# BrushlessLamp.net
KiCad netlist of a schematic drawn in EAGLE
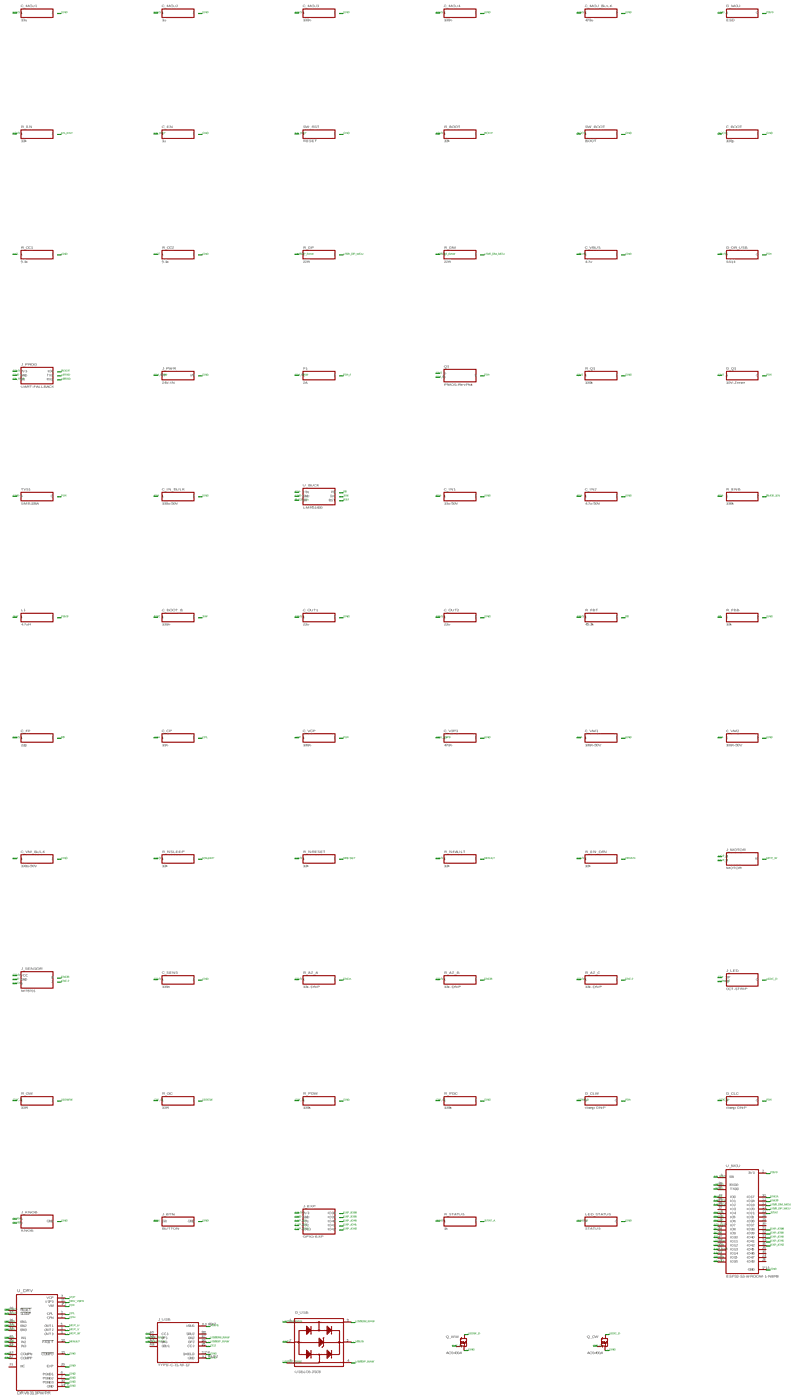
[diagram p0: schematic, sheet 1, overview]
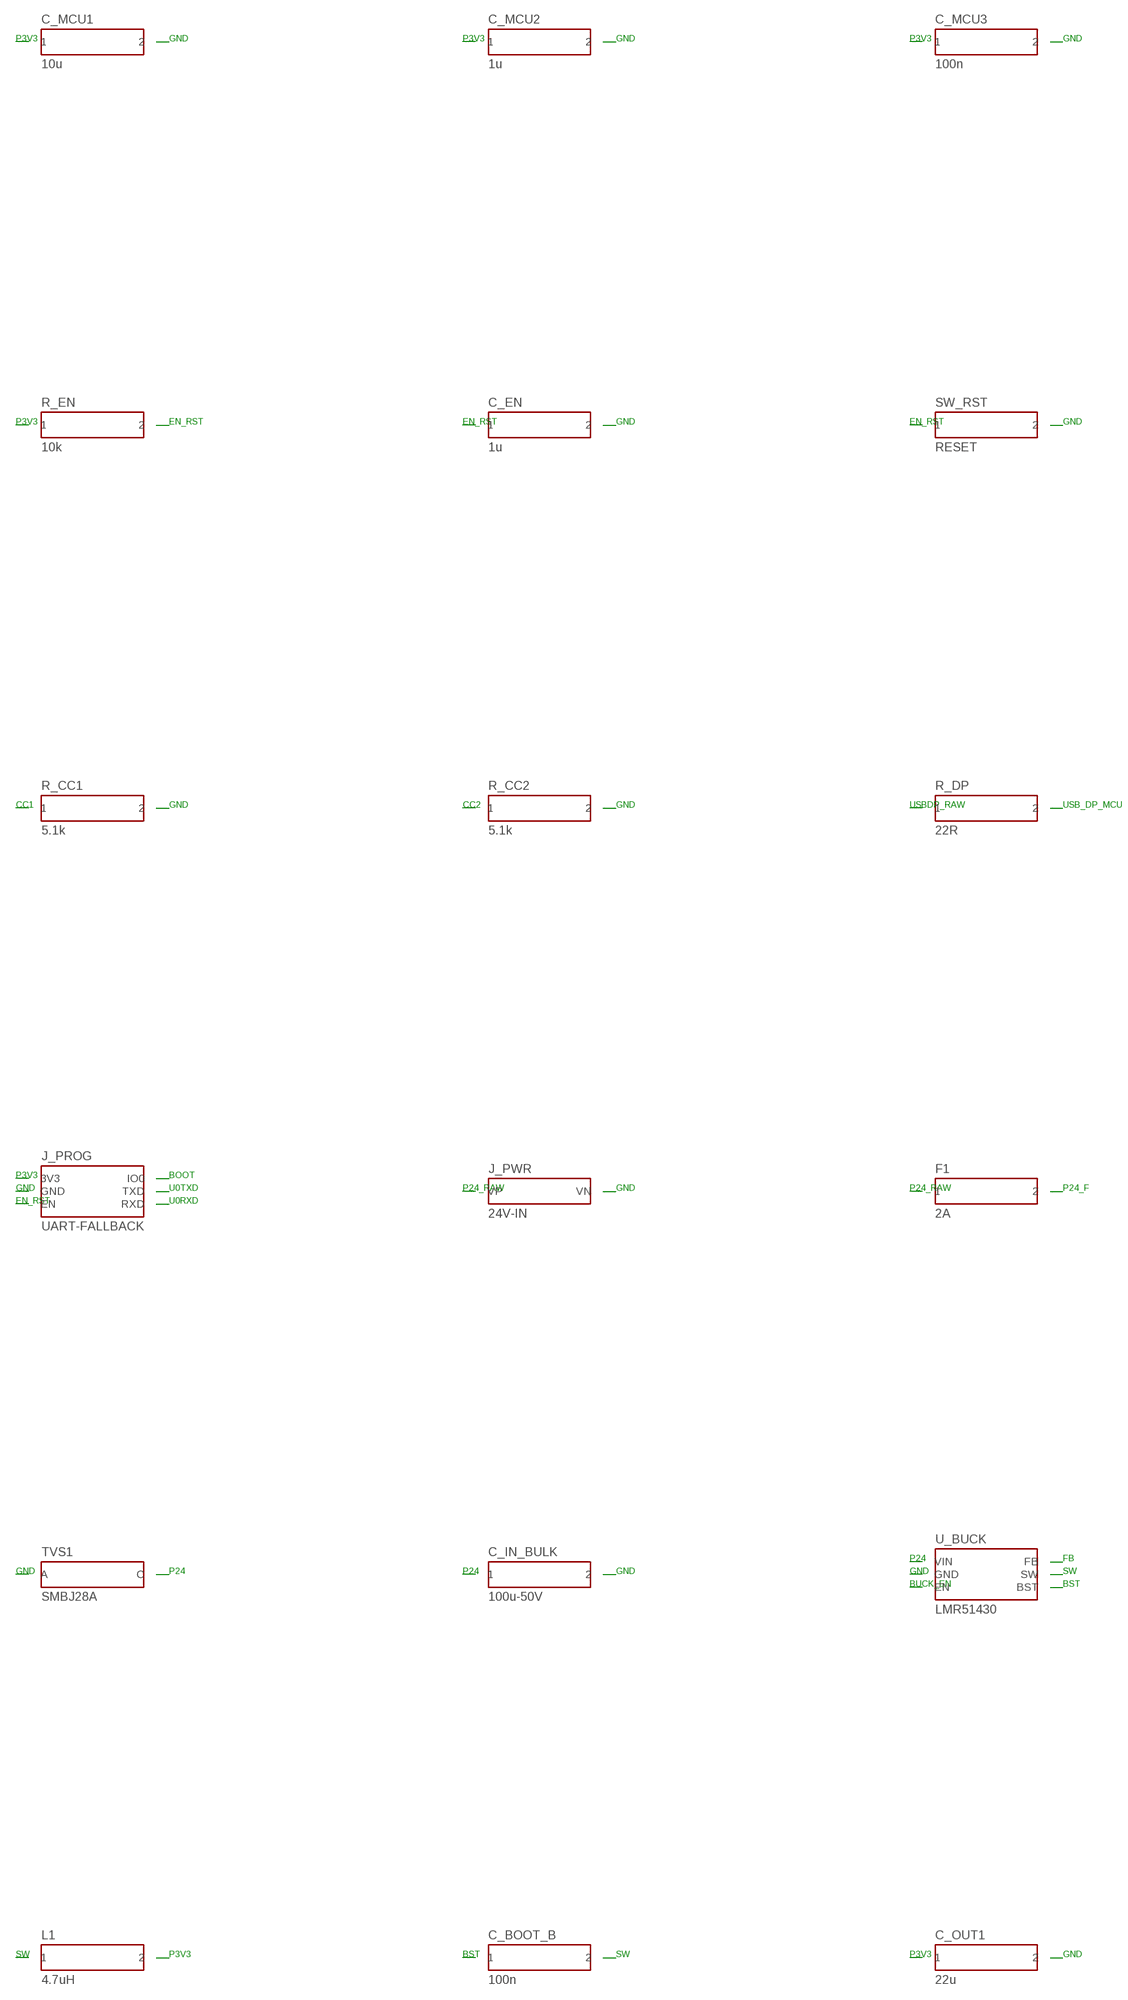
[diagram p1: schematic, sheet 1, part 1 of 4]
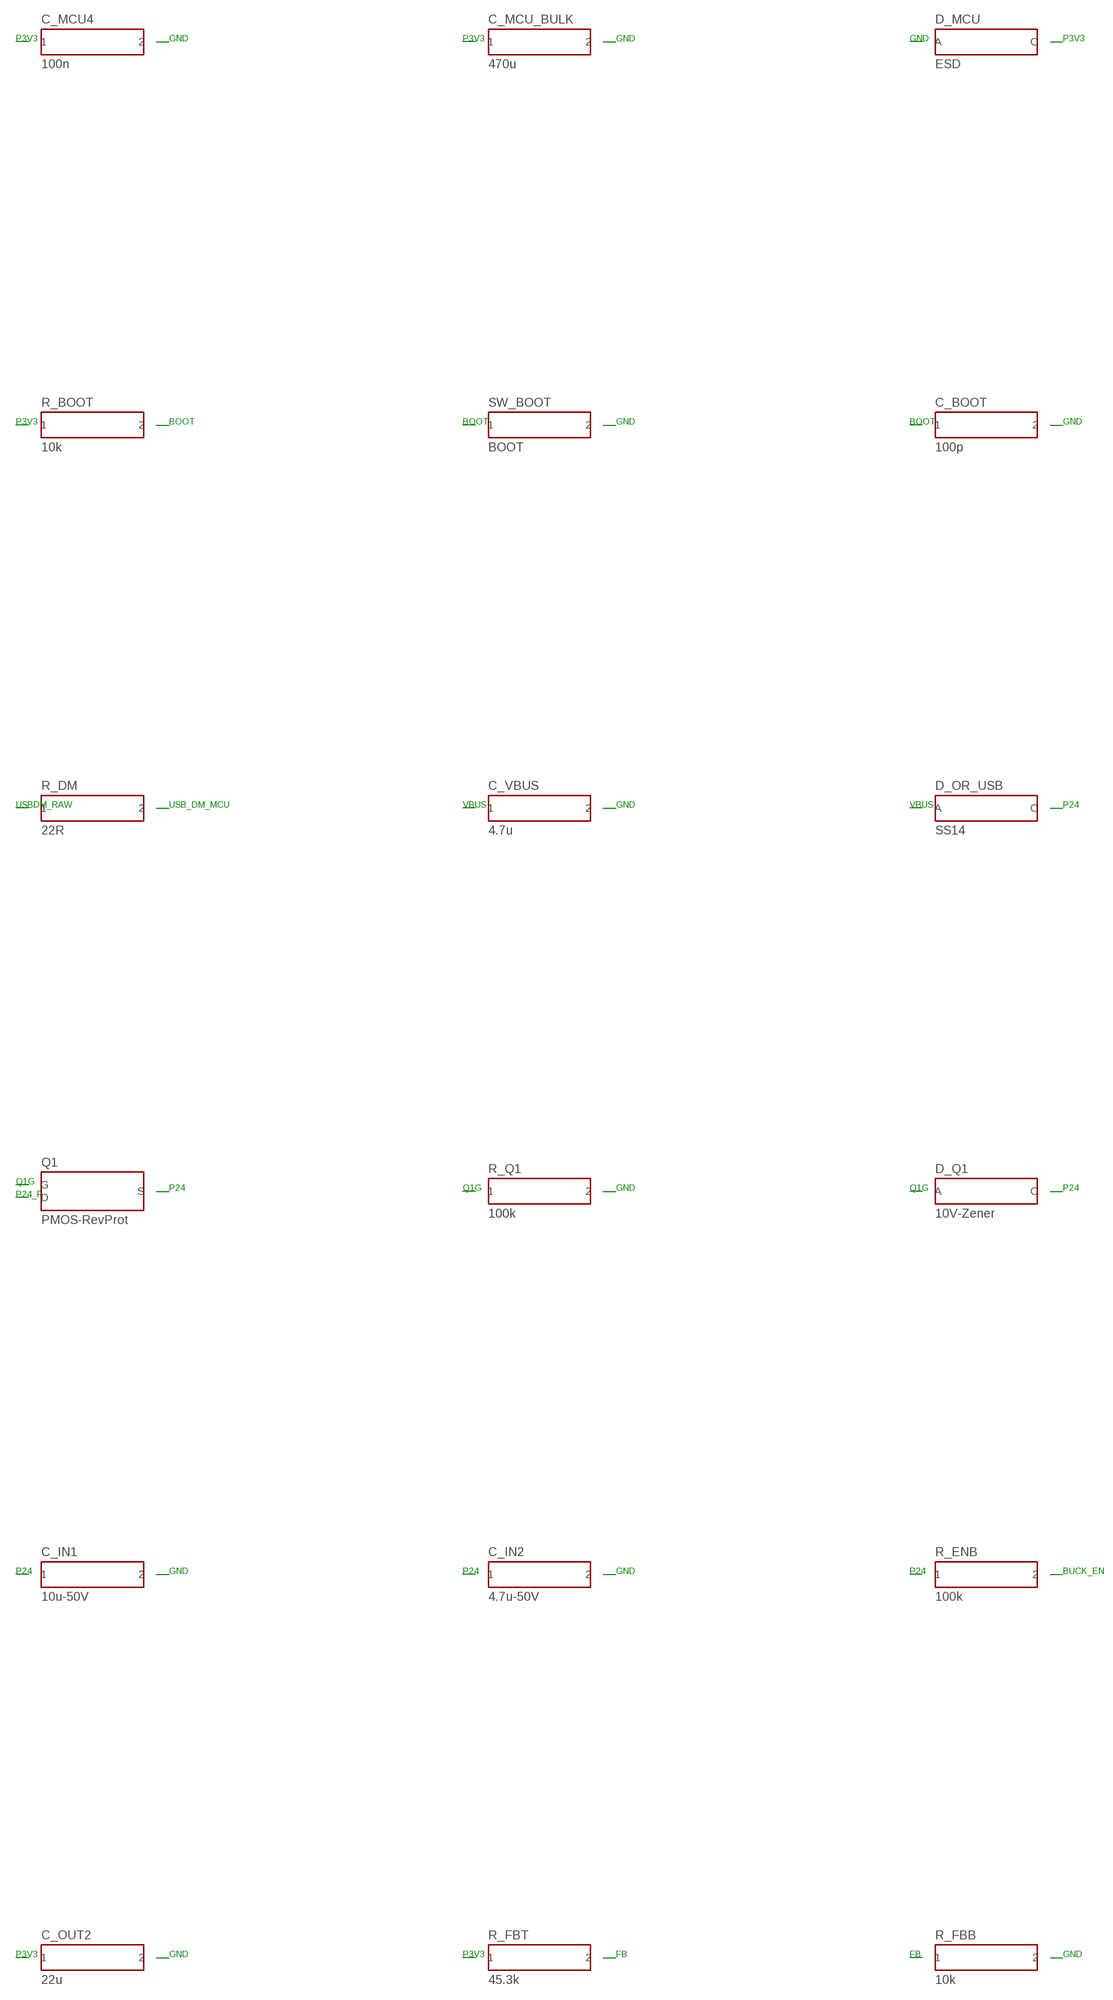
[diagram p2: schematic, sheet 1, part 2 of 4]
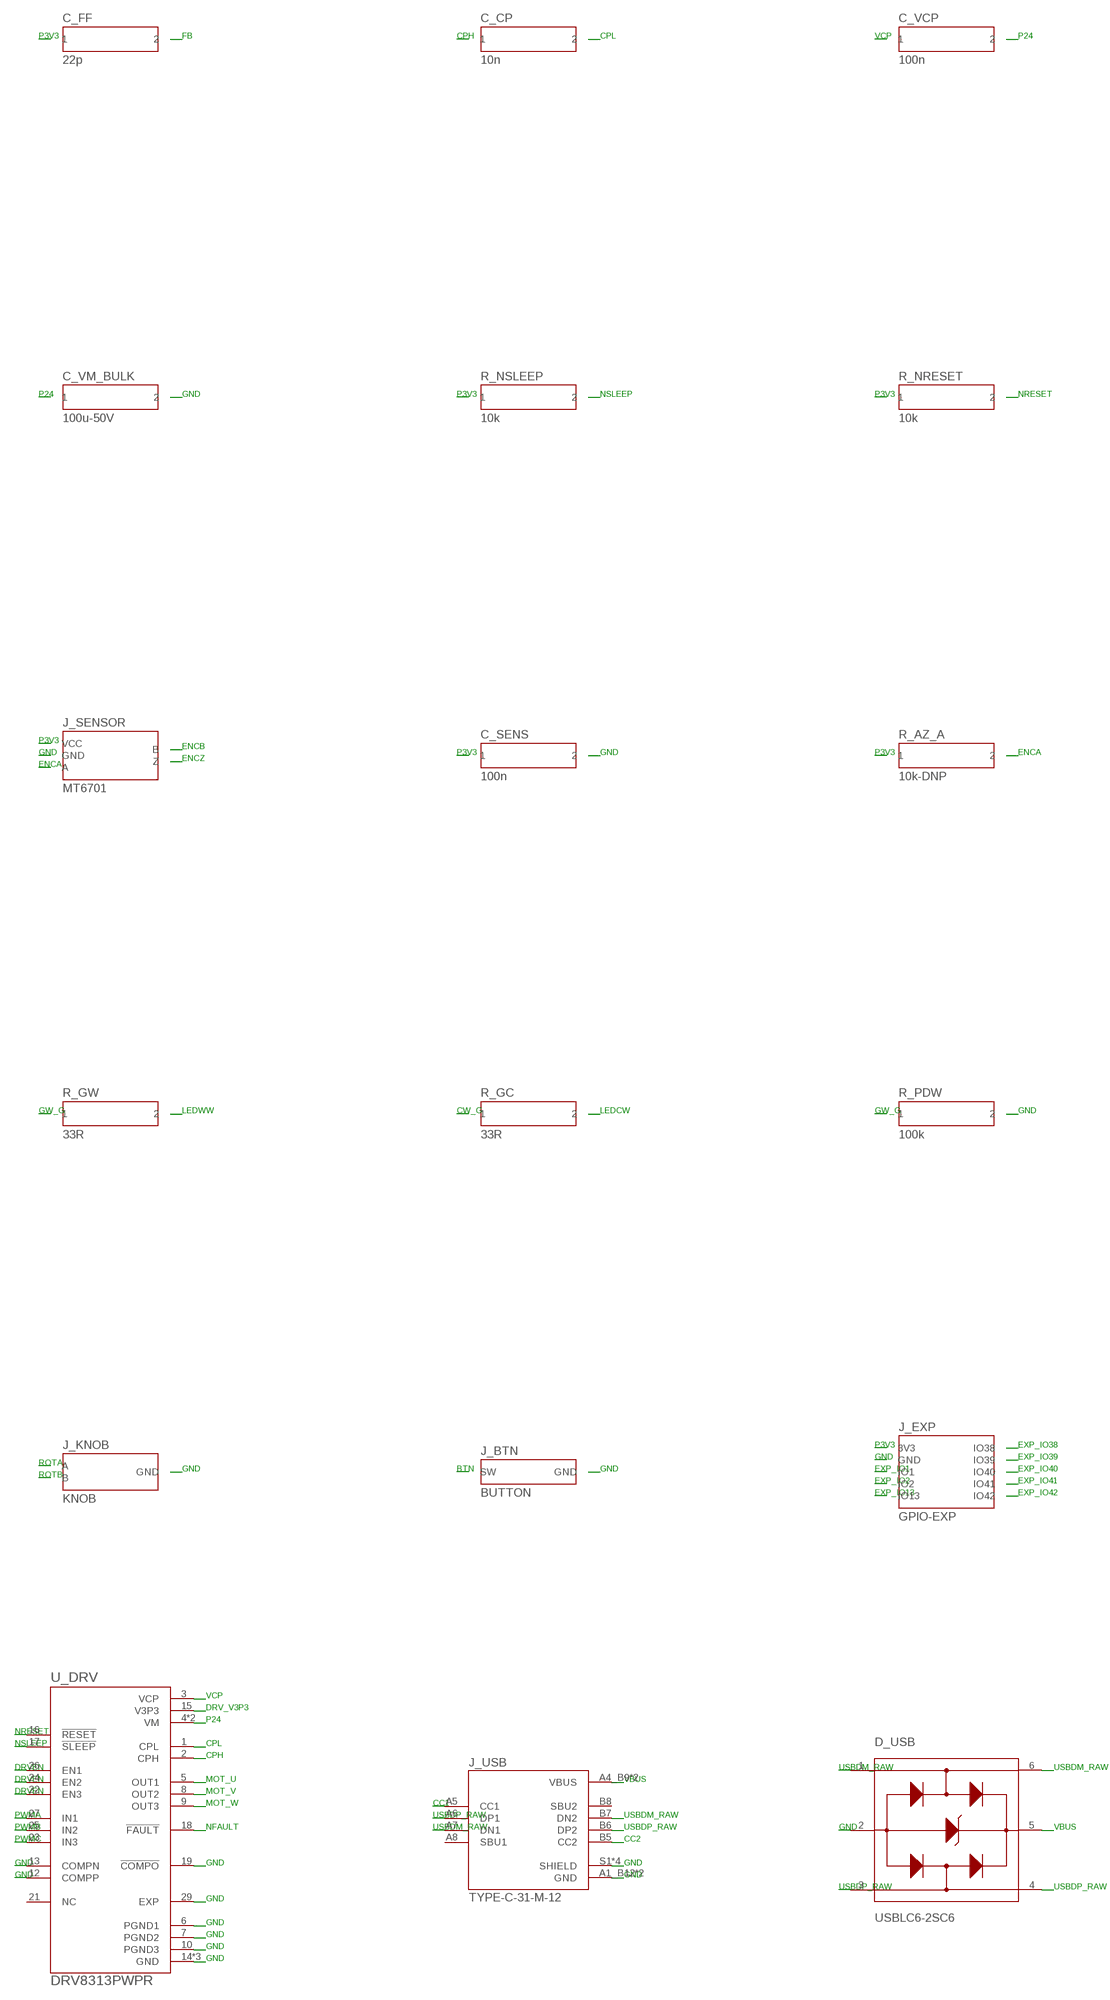
[diagram p3: schematic, sheet 1, part 3 of 4]
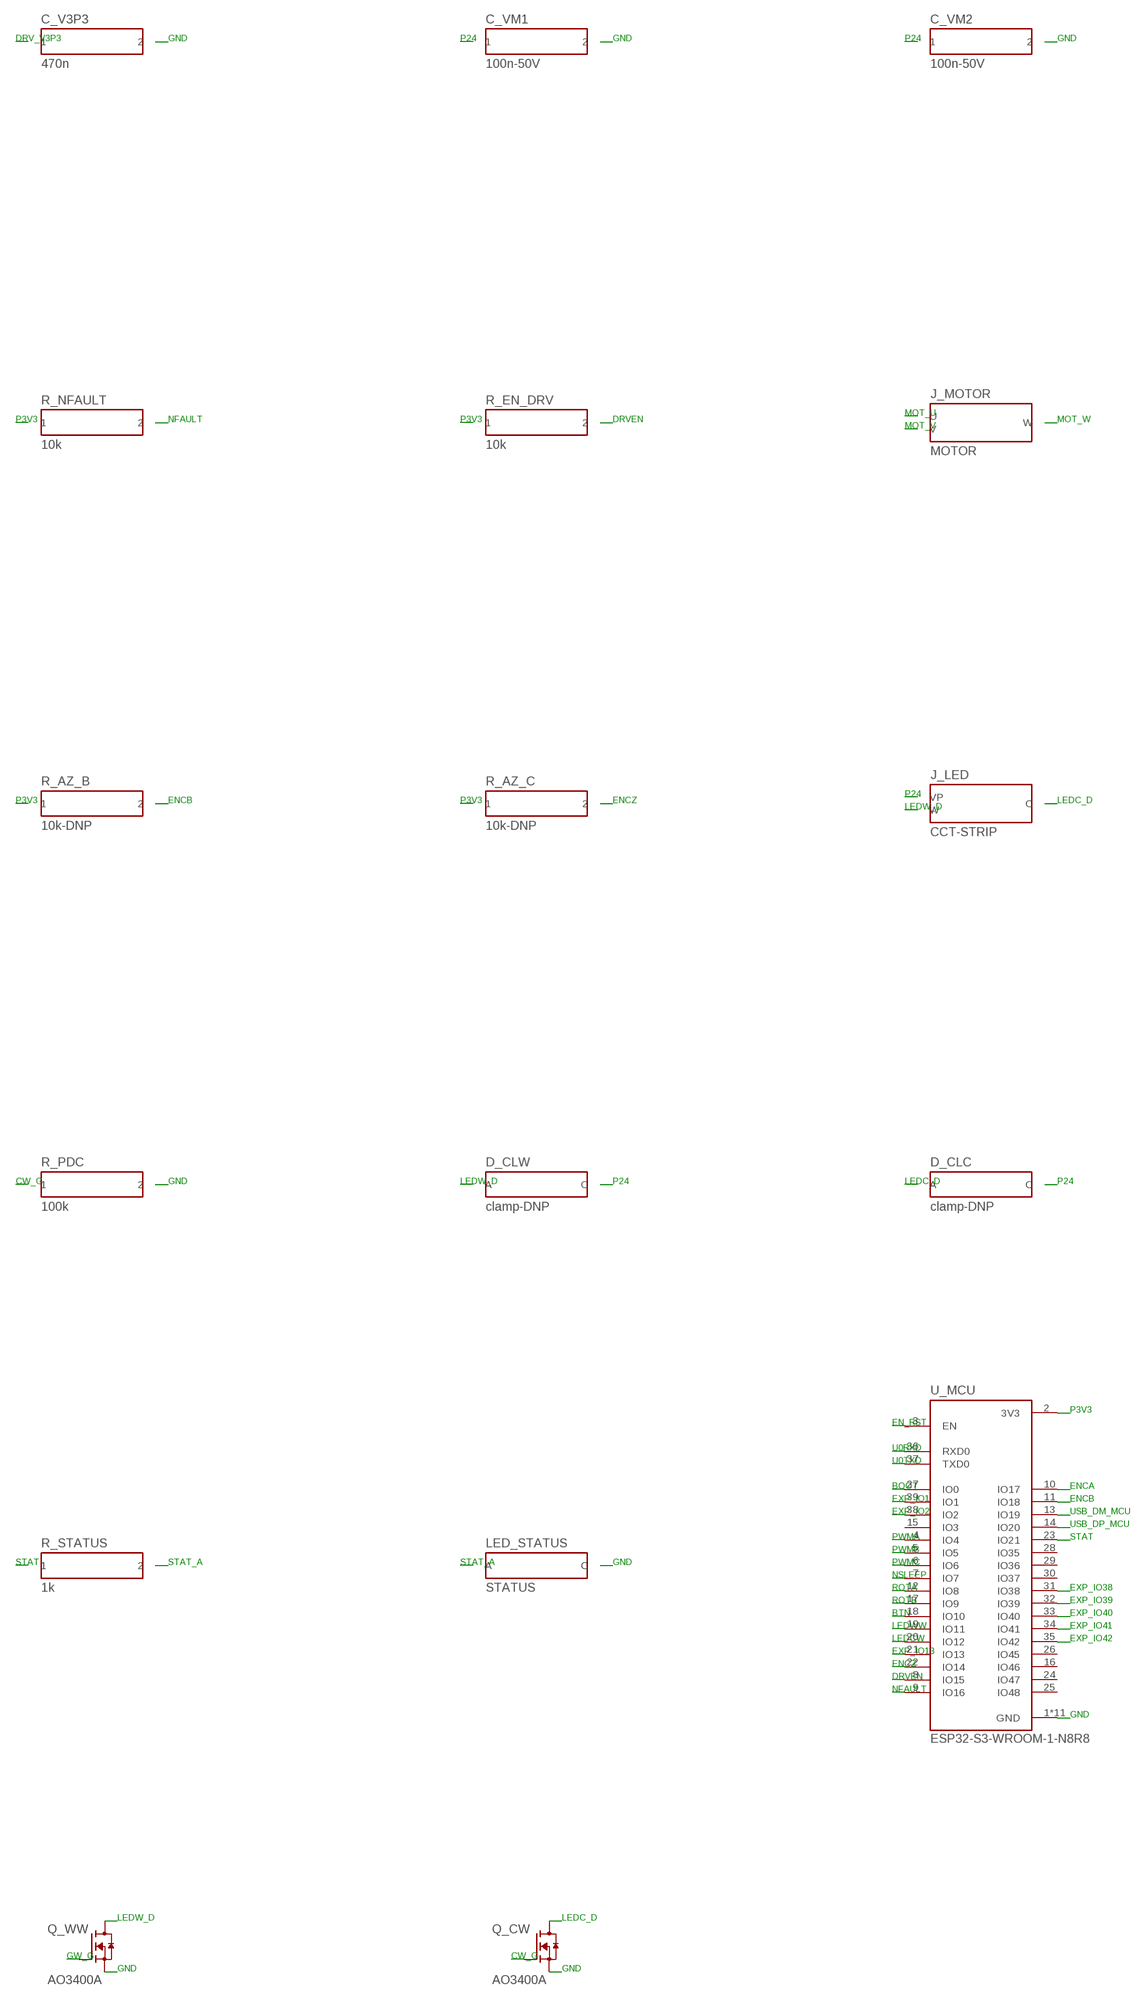
[diagram p4: schematic, sheet 1, part 4 of 4]

(export (version "E")
  (design (tool "Eeschema 10.0.6"))
  (components
    (comp (ref "C_BOOT")
      (value "100p")
      (footprint "eagle-import:0402")
      (libsource (lib "eagle-import") (part "CAP_0402"))
    )
    (comp (ref "C_BOOT_B")
      (value "100n")
      (footprint "eagle-import:0402")
      (libsource (lib "eagle-import") (part "CAP_0402"))
    )
    (comp (ref "C_CP")
      (value "10n")
      (footprint "eagle-import:0603")
      (libsource (lib "eagle-import") (part "CAP_0603"))
    )
    (comp (ref "C_EN")
      (value "1u")
      (footprint "eagle-import:0603")
      (libsource (lib "eagle-import") (part "CAP_0603"))
    )
    (comp (ref "C_FF")
      (value "22p")
      (footprint "eagle-import:0402")
      (libsource (lib "eagle-import") (part "CAP_0402"))
    )
    (comp (ref "C_IN1")
      (value "10u-50V")
      (footprint "eagle-import:1210")
      (libsource (lib "eagle-import") (part "CAP_1210"))
    )
    (comp (ref "C_IN2")
      (value "4.7u-50V")
      (footprint "eagle-import:1206")
      (libsource (lib "eagle-import") (part "CAP_1206"))
    )
    (comp (ref "C_IN_BULK")
      (value "100u-50V")
      (footprint "eagle-import:CAP_V")
      (libsource (lib "eagle-import") (part "CAP_V"))
    )
    (comp (ref "C_MCU1")
      (value "10u")
      (footprint "eagle-import:0805")
      (libsource (lib "eagle-import") (part "CAP_0805"))
    )
    (comp (ref "C_MCU2")
      (value "1u")
      (footprint "eagle-import:0603")
      (libsource (lib "eagle-import") (part "CAP_0603"))
    )
    (comp (ref "C_MCU3")
      (value "100n")
      (footprint "eagle-import:0402")
      (libsource (lib "eagle-import") (part "CAP_0402"))
    )
    (comp (ref "C_MCU4")
      (value "100n")
      (footprint "eagle-import:0402")
      (libsource (lib "eagle-import") (part "CAP_0402"))
    )
    (comp (ref "C_MCU_BULK")
      (value "470u")
      (footprint "eagle-import:CAP_D")
      (libsource (lib "eagle-import") (part "CAP_D"))
    )
    (comp (ref "C_OUT1")
      (value "22u")
      (footprint "eagle-import:0805")
      (libsource (lib "eagle-import") (part "CAP_0805"))
    )
    (comp (ref "C_OUT2")
      (value "22u")
      (footprint "eagle-import:0805")
      (libsource (lib "eagle-import") (part "CAP_0805"))
    )
    (comp (ref "C_SENS")
      (value "100n")
      (footprint "eagle-import:0402")
      (libsource (lib "eagle-import") (part "CAP_0402"))
    )
    (comp (ref "C_V3P3")
      (value "470n")
      (footprint "eagle-import:0603")
      (libsource (lib "eagle-import") (part "CAP_0603"))
    )
    (comp (ref "C_VBUS")
      (value "4.7u")
      (footprint "eagle-import:0603")
      (libsource (lib "eagle-import") (part "CAP_0603"))
    )
    (comp (ref "C_VCP")
      (value "100n")
      (footprint "eagle-import:0603")
      (libsource (lib "eagle-import") (part "CAP_0603"))
    )
    (comp (ref "C_VM1")
      (value "100n-50V")
      (footprint "eagle-import:0603")
      (libsource (lib "eagle-import") (part "CAP_0603"))
    )
    (comp (ref "C_VM2")
      (value "100n-50V")
      (footprint "eagle-import:0603")
      (libsource (lib "eagle-import") (part "CAP_0603"))
    )
    (comp (ref "C_VM_BULK")
      (value "100u-50V")
      (footprint "eagle-import:CAP_V")
      (libsource (lib "eagle-import") (part "CAP_V"))
    )
    (comp (ref "D_CLC")
      (value "clamp-DNP")
      (footprint "eagle-import:SOD323")
      (libsource (lib "eagle-import") (part "DIODE_SOD323"))
    )
    (comp (ref "D_CLW")
      (value "clamp-DNP")
      (footprint "eagle-import:SOD323")
      (libsource (lib "eagle-import") (part "DIODE_SOD323"))
    )
    (comp (ref "D_MCU")
      (value "ESD")
      (footprint "eagle-import:SOD323")
      (libsource (lib "eagle-import") (part "DIODE_SOD323"))
    )
    (comp (ref "D_OR_USB")
      (value "SS14")
      (footprint "eagle-import:SMA")
      (libsource (lib "eagle-import") (part "DIODE_SMA"))
    )
    (comp (ref "D_Q1")
      (value "10V-Zener")
      (footprint "eagle-import:SOD123")
      (libsource (lib "eagle-import") (part "DIODE_SOD123"))
    )
    (comp (ref "D_USB")
      (value "USBLC6-2SC6")
      (footprint "eagle-import:SOT95P280X145-6N")
      (fields (field (name "MF") "STMicroelectronics"))
      (libsource (lib "eagle-import") (part "USBLC6-2SC6"))
    )
    (comp (ref "F1")
      (value "2A")
      (footprint "eagle-import:FUSENANO2")
      (libsource (lib "eagle-import") (part "FUSE_NANO2"))
    )
    (comp (ref "J_BTN")
      (value "BUTTON")
      (footprint "eagle-import:XH2")
      (libsource (lib "eagle-import") (part "CONN_BTN_DS"))
    )
    (comp (ref "J_EXP")
      (value "GPIO-EXP")
      (footprint "eagle-import:HDR10")
      (libsource (lib "eagle-import") (part "CONN_EXP_DS"))
    )
    (comp (ref "J_KNOB")
      (value "KNOB")
      (footprint "eagle-import:XH3")
      (libsource (lib "eagle-import") (part "CONN_KNOB_DS"))
    )
    (comp (ref "J_LED")
      (value "CCT-STRIP")
      (footprint "eagle-import:XH3")
      (libsource (lib "eagle-import") (part "CONN_LED_DS"))
    )
    (comp (ref "J_MOTOR")
      (value "MOTOR")
      (footprint "eagle-import:SCREW3")
      (libsource (lib "eagle-import") (part "CONN_MOTOR_DS"))
    )
    (comp (ref "J_PROG")
      (value "UART-FALLBACK")
      (footprint "eagle-import:HDR6")
      (libsource (lib "eagle-import") (part "CONN_PROG_DS"))
    )
    (comp (ref "J_PWR")
      (value "24V-IN")
      (footprint "eagle-import:SCREW2")
      (libsource (lib "eagle-import") (part "CONN_PWR_DS"))
    )
    (comp (ref "J_SENSOR")
      (value "MT6701")
      (footprint "eagle-import:SCREW5")
      (libsource (lib "eagle-import") (part "CONN_SENSOR_DS"))
    )
    (comp (ref "J_USB")
      (value "TYPE-C-31-M-12")
      (footprint "eagle-import:HRO_TYPE-C-31-M-12")
      (fields (field (name "MF") "HRO Electronics Co., Ltd."))
      (libsource (lib "eagle-import") (part "TYPE-C-31-M-12"))
    )
    (comp (ref "L1")
      (value "4.7uH")
      (footprint "eagle-import:IND43")
      (libsource (lib "eagle-import") (part "IND_SMD"))
    )
    (comp (ref "LED_STATUS")
      (value "STATUS")
      (footprint "eagle-import:LED0603")
      (libsource (lib "eagle-import") (part "LED_0603"))
    )
    (comp (ref "Q1")
      (value "PMOS-RevProt")
      (footprint "eagle-import:SOT23")
      (libsource (lib "eagle-import") (part "FET_SOT23"))
    )
    (comp (ref "Q_CW")
      (value "AO3400A")
      (footprint "eagle-import:SOT95P280X125-3N")
      (fields (field (name "MF") "UMW"))
      (libsource (lib "eagle-import") (part "AO3400A"))
    )
    (comp (ref "Q_WW")
      (value "AO3400A")
      (footprint "eagle-import:SOT95P280X125-3N")
      (fields (field (name "MF") "UMW"))
      (libsource (lib "eagle-import") (part "AO3400A"))
    )
    (comp (ref "R_AZ_A")
      (value "10k-DNP")
      (footprint "eagle-import:0603")
      (libsource (lib "eagle-import") (part "RES_0603"))
    )
    (comp (ref "R_AZ_B")
      (value "10k-DNP")
      (footprint "eagle-import:0603")
      (libsource (lib "eagle-import") (part "RES_0603"))
    )
    (comp (ref "R_AZ_C")
      (value "10k-DNP")
      (footprint "eagle-import:0603")
      (libsource (lib "eagle-import") (part "RES_0603"))
    )
    (comp (ref "R_BOOT")
      (value "10k")
      (footprint "eagle-import:0603")
      (libsource (lib "eagle-import") (part "RES_0603"))
    )
    (comp (ref "R_CC1")
      (value "5.1k")
      (footprint "eagle-import:0603")
      (libsource (lib "eagle-import") (part "RES_0603"))
    )
    (comp (ref "R_CC2")
      (value "5.1k")
      (footprint "eagle-import:0603")
      (libsource (lib "eagle-import") (part "RES_0603"))
    )
    (comp (ref "R_DM")
      (value "22R")
      (footprint "eagle-import:0603")
      (libsource (lib "eagle-import") (part "RES_0603"))
    )
    (comp (ref "R_DP")
      (value "22R")
      (footprint "eagle-import:0603")
      (libsource (lib "eagle-import") (part "RES_0603"))
    )
    (comp (ref "R_EN")
      (value "10k")
      (footprint "eagle-import:0603")
      (libsource (lib "eagle-import") (part "RES_0603"))
    )
    (comp (ref "R_ENB")
      (value "100k")
      (footprint "eagle-import:0603")
      (libsource (lib "eagle-import") (part "RES_0603"))
    )
    (comp (ref "R_EN_DRV")
      (value "10k")
      (footprint "eagle-import:0603")
      (libsource (lib "eagle-import") (part "RES_0603"))
    )
    (comp (ref "R_FBB")
      (value "10k")
      (footprint "eagle-import:0603")
      (libsource (lib "eagle-import") (part "RES_0603"))
    )
    (comp (ref "R_FBT")
      (value "45.3k")
      (footprint "eagle-import:0603")
      (libsource (lib "eagle-import") (part "RES_0603"))
    )
    (comp (ref "R_GC")
      (value "33R")
      (footprint "eagle-import:0603")
      (libsource (lib "eagle-import") (part "RES_0603"))
    )
    (comp (ref "R_GW")
      (value "33R")
      (footprint "eagle-import:0603")
      (libsource (lib "eagle-import") (part "RES_0603"))
    )
    (comp (ref "R_NFAULT")
      (value "10k")
      (footprint "eagle-import:0603")
      (libsource (lib "eagle-import") (part "RES_0603"))
    )
    (comp (ref "R_NRESET")
      (value "10k")
      (footprint "eagle-import:0603")
      (libsource (lib "eagle-import") (part "RES_0603"))
    )
    (comp (ref "R_NSLEEP")
      (value "10k")
      (footprint "eagle-import:0603")
      (libsource (lib "eagle-import") (part "RES_0603"))
    )
    (comp (ref "R_PDC")
      (value "100k")
      (footprint "eagle-import:0603")
      (libsource (lib "eagle-import") (part "RES_0603"))
    )
    (comp (ref "R_PDW")
      (value "100k")
      (footprint "eagle-import:0603")
      (libsource (lib "eagle-import") (part "RES_0603"))
    )
    (comp (ref "R_Q1")
      (value "100k")
      (footprint "eagle-import:0603")
      (libsource (lib "eagle-import") (part "RES_0603"))
    )
    (comp (ref "R_STATUS")
      (value "1k")
      (footprint "eagle-import:0603")
      (libsource (lib "eagle-import") (part "RES_0603"))
    )
    (comp (ref "SW_BOOT")
      (value "BOOT")
      (footprint "eagle-import:TACT")
      (libsource (lib "eagle-import") (part "SW_TACT"))
    )
    (comp (ref "SW_RST")
      (value "RESET")
      (footprint "eagle-import:TACT")
      (libsource (lib "eagle-import") (part "SW_TACT"))
    )
    (comp (ref "TVS1")
      (value "SMBJ28A")
      (footprint "eagle-import:SMB")
      (libsource (lib "eagle-import") (part "DIODE_SMB"))
    )
    (comp (ref "U_BUCK")
      (value "LMR51430")
      (footprint "eagle-import:SOT236")
      (libsource (lib "eagle-import") (part "BUCK_DS"))
    )
    (comp (ref "U_DRV")
      (value "DRV8313PWPR")
      (footprint "eagle-import:SOP65P640X120-29N")
      (fields (field (name "MF") "Texas Instruments"))
      (libsource (lib "eagle-import") (part "DRV8313PWPR"))
    )
    (comp (ref "U_MCU")
      (value "ESP32-S3-WROOM-1-N8R8")
      (footprint "eagle-import:XCVR_ESP32S3WROOM1N8R8")
      (fields (field (name "MF") "Espressif Systems"))
      (libsource (lib "eagle-import") (part "ESP32-S3-WROOM-1-N8R8"))
    )
  )
  (nets
    (net (code "1") (name "/BOOT") (class "Default")
      (node (ref "C_BOOT") (pin "1") (pinfunction "1_1") (pintype "passive"))
      (node (ref "J_PROG") (pin "4") (pinfunction "IO0_4") (pintype "passive"))
      (node (ref "R_BOOT") (pin "2") (pinfunction "2_2") (pintype "passive"))
      (node (ref "SW_BOOT") (pin "1") (pinfunction "1_1") (pintype "passive"))
      (node (ref "SW_BOOT") (pin "3") (pinfunction "1_3") (pintype "passive"))
      (node (ref "U_MCU") (pin "27") (pinfunction "IO0_27") (pintype "bidirectional"))
    )
    (net (code "2") (name "/BST") (class "Default")
      (node (ref "C_BOOT_B") (pin "1") (pinfunction "1_1") (pintype "passive"))
      (node (ref "U_BUCK") (pin "6") (pinfunction "BST_6") (pintype "passive"))
    )
    (net (code "3") (name "/BTN") (class "Default")
      (node (ref "J_BTN") (pin "1") (pinfunction "SW_1") (pintype "passive"))
      (node (ref "U_MCU") (pin "18") (pinfunction "IO10_18") (pintype "bidirectional"))
    )
    (net (code "4") (name "/BUCK_EN") (class "Default")
      (node (ref "R_ENB") (pin "2") (pinfunction "2_2") (pintype "passive"))
      (node (ref "U_BUCK") (pin "5") (pinfunction "EN_5") (pintype "passive"))
    )
    (net (code "5") (name "/CC1") (class "Default")
      (node (ref "J_USB") (pin "A5") (pinfunction "CC1_A5") (pintype "bidirectional"))
      (node (ref "R_CC1") (pin "1") (pinfunction "1_1") (pintype "passive"))
    )
    (net (code "6") (name "/CC2") (class "Default")
      (node (ref "J_USB") (pin "B5") (pinfunction "CC2_B5") (pintype "bidirectional"))
      (node (ref "R_CC2") (pin "1") (pinfunction "1_1") (pintype "passive"))
    )
    (net (code "7") (name "/CPH") (class "Default")
      (node (ref "C_CP") (pin "1") (pinfunction "1_1") (pintype "passive"))
      (node (ref "U_DRV") (pin "2") (pinfunction "CPH_2") (pintype "power_in"))
    )
    (net (code "8") (name "/CPL") (class "Default")
      (node (ref "C_CP") (pin "2") (pinfunction "2_2") (pintype "passive"))
      (node (ref "U_DRV") (pin "1") (pinfunction "CPL_1") (pintype "power_in"))
    )
    (net (code "9") (name "/CW_G") (class "Default")
      (node (ref "Q_CW") (pin "1") (pinfunction "G_1") (pintype "passive"))
      (node (ref "R_GC") (pin "1") (pinfunction "1_1") (pintype "passive"))
      (node (ref "R_PDC") (pin "1") (pinfunction "1_1") (pintype "passive"))
    )
    (net (code "10") (name "/DRVEN") (class "Default")
      (node (ref "R_EN_DRV") (pin "2") (pinfunction "2_2") (pintype "passive"))
      (node (ref "U_DRV") (pin "22") (pinfunction "EN3_22") (pintype "input"))
      (node (ref "U_DRV") (pin "24") (pinfunction "EN2_24") (pintype "input"))
      (node (ref "U_DRV") (pin "26") (pinfunction "EN1_26") (pintype "input"))
      (node (ref "U_MCU") (pin "8") (pinfunction "IO15_8") (pintype "bidirectional"))
    )
    (net (code "11") (name "/DRV_V3P3") (class "Default")
      (node (ref "C_V3P3") (pin "1") (pinfunction "1_1") (pintype "passive"))
      (node (ref "U_DRV") (pin "15") (pinfunction "V3P3_15") (pintype "power_in"))
    )
    (net (code "12") (name "/ENCA") (class "Default")
      (node (ref "J_SENSOR") (pin "3") (pinfunction "A_3") (pintype "passive"))
      (node (ref "R_AZ_A") (pin "2") (pinfunction "2_2") (pintype "passive"))
      (node (ref "U_MCU") (pin "10") (pinfunction "IO17_10") (pintype "bidirectional"))
    )
    (net (code "13") (name "/ENCB") (class "Default")
      (node (ref "J_SENSOR") (pin "4") (pinfunction "B_4") (pintype "passive"))
      (node (ref "R_AZ_B") (pin "2") (pinfunction "2_2") (pintype "passive"))
      (node (ref "U_MCU") (pin "11") (pinfunction "IO18_11") (pintype "bidirectional"))
    )
    (net (code "14") (name "/ENCZ") (class "Default")
      (node (ref "J_SENSOR") (pin "5") (pinfunction "Z_5") (pintype "passive"))
      (node (ref "R_AZ_C") (pin "2") (pinfunction "2_2") (pintype "passive"))
      (node (ref "U_MCU") (pin "22") (pinfunction "IO14_22") (pintype "bidirectional"))
    )
    (net (code "15") (name "/EN_RST") (class "Default")
      (node (ref "C_EN") (pin "1") (pinfunction "1_1") (pintype "passive"))
      (node (ref "J_PROG") (pin "3") (pinfunction "EN_3") (pintype "passive"))
      (node (ref "R_EN") (pin "2") (pinfunction "2_2") (pintype "passive"))
      (node (ref "SW_RST") (pin "1") (pinfunction "1_1") (pintype "passive"))
      (node (ref "SW_RST") (pin "3") (pinfunction "1_3") (pintype "passive"))
      (node (ref "U_MCU") (pin "3") (pinfunction "EN_3") (pintype "input"))
    )
    (net (code "16") (name "/EXP_IO1") (class "Default")
      (node (ref "J_EXP") (pin "3") (pinfunction "IO1_3") (pintype "passive"))
      (node (ref "U_MCU") (pin "39") (pinfunction "IO1_39") (pintype "bidirectional"))
    )
    (net (code "17") (name "/EXP_IO2") (class "Default")
      (node (ref "J_EXP") (pin "4") (pinfunction "IO2_4") (pintype "passive"))
      (node (ref "U_MCU") (pin "38") (pinfunction "IO2_38") (pintype "bidirectional"))
    )
    (net (code "18") (name "/EXP_IO13") (class "Default")
      (node (ref "J_EXP") (pin "5") (pinfunction "IO13_5") (pintype "passive"))
      (node (ref "U_MCU") (pin "21") (pinfunction "IO13_21") (pintype "bidirectional"))
    )
    (net (code "19") (name "/EXP_IO38") (class "Default")
      (node (ref "J_EXP") (pin "6") (pinfunction "IO38_6") (pintype "passive"))
      (node (ref "U_MCU") (pin "31") (pinfunction "IO38_31") (pintype "bidirectional"))
    )
    (net (code "20") (name "/EXP_IO39") (class "Default")
      (node (ref "J_EXP") (pin "7") (pinfunction "IO39_7") (pintype "passive"))
      (node (ref "U_MCU") (pin "32") (pinfunction "IO39_32") (pintype "bidirectional"))
    )
    (net (code "21") (name "/EXP_IO40") (class "Default")
      (node (ref "J_EXP") (pin "8") (pinfunction "IO40_8") (pintype "passive"))
      (node (ref "U_MCU") (pin "33") (pinfunction "IO40_33") (pintype "bidirectional"))
    )
    (net (code "22") (name "/EXP_IO41") (class "Default")
      (node (ref "J_EXP") (pin "9") (pinfunction "IO41_9") (pintype "passive"))
      (node (ref "U_MCU") (pin "34") (pinfunction "IO41_34") (pintype "bidirectional"))
    )
    (net (code "23") (name "/EXP_IO42") (class "Default")
      (node (ref "J_EXP") (pin "10") (pinfunction "IO42_10") (pintype "passive"))
      (node (ref "U_MCU") (pin "35") (pinfunction "IO42_35") (pintype "bidirectional"))
    )
    (net (code "24") (name "/FB") (class "Default")
      (node (ref "C_FF") (pin "2") (pinfunction "2_2") (pintype "passive"))
      (node (ref "R_FBB") (pin "1") (pinfunction "1_1") (pintype "passive"))
      (node (ref "R_FBT") (pin "2") (pinfunction "2_2") (pintype "passive"))
      (node (ref "U_BUCK") (pin "4") (pinfunction "FB_4") (pintype "passive"))
    )
    (net (code "25") (name "/GND") (class "Default")
      (node (ref "C_BOOT") (pin "2") (pinfunction "2_2") (pintype "passive"))
      (node (ref "C_EN") (pin "2") (pinfunction "2_2") (pintype "passive"))
      (node (ref "C_IN1") (pin "2") (pinfunction "2_2") (pintype "passive"))
      (node (ref "C_IN2") (pin "2") (pinfunction "2_2") (pintype "passive"))
      (node (ref "C_IN_BULK") (pin "2") (pinfunction "2_2") (pintype "passive"))
      (node (ref "C_MCU1") (pin "2") (pinfunction "2_2") (pintype "passive"))
      (node (ref "C_MCU2") (pin "2") (pinfunction "2_2") (pintype "passive"))
      (node (ref "C_MCU3") (pin "2") (pinfunction "2_2") (pintype "passive"))
      (node (ref "C_MCU4") (pin "2") (pinfunction "2_2") (pintype "passive"))
      (node (ref "C_MCU_BULK") (pin "2") (pinfunction "2_2") (pintype "passive"))
      (node (ref "C_OUT1") (pin "2") (pinfunction "2_2") (pintype "passive"))
      (node (ref "C_OUT2") (pin "2") (pinfunction "2_2") (pintype "passive"))
      (node (ref "C_SENS") (pin "2") (pinfunction "2_2") (pintype "passive"))
      (node (ref "C_V3P3") (pin "2") (pinfunction "2_2") (pintype "passive"))
      (node (ref "C_VBUS") (pin "2") (pinfunction "2_2") (pintype "passive"))
      (node (ref "C_VM1") (pin "2") (pinfunction "2_2") (pintype "passive"))
      (node (ref "C_VM2") (pin "2") (pinfunction "2_2") (pintype "passive"))
      (node (ref "C_VM_BULK") (pin "2") (pinfunction "2_2") (pintype "passive"))
      (node (ref "D_MCU") (pin "A") (pinfunction "A_A") (pintype "passive"))
      (node (ref "D_USB") (pin "2") (pinfunction "GND_2") (pintype "power_in"))
      (node (ref "J_BTN") (pin "2") (pinfunction "GND_2") (pintype "passive"))
      (node (ref "J_EXP") (pin "2") (pinfunction "GND_2") (pintype "passive"))
      (node (ref "J_KNOB") (pin "3") (pinfunction "GND_3") (pintype "passive"))
      (node (ref "J_PROG") (pin "2") (pinfunction "GND_2") (pintype "passive"))
      (node (ref "J_PWR") (pin "2") (pinfunction "VN_2") (pintype "passive"))
      (node (ref "J_SENSOR") (pin "2") (pinfunction "GND_2") (pintype "passive"))
      (node (ref "J_USB") (pin "A1_B12") (pinfunction "GND_A1_B12") (pintype "power_in"))
      (node (ref "J_USB") (pin "B1_A12") (pinfunction "GND_B1_A12") (pintype "power_in"))
      (node (ref "J_USB") (pin "S1") (pinfunction "SHIELD_S1") (pintype "passive"))
      (node (ref "J_USB") (pin "S2") (pinfunction "SHIELD_S2") (pintype "passive"))
      (node (ref "J_USB") (pin "S3") (pinfunction "SHIELD_S3") (pintype "passive"))
      (node (ref "J_USB") (pin "S4") (pinfunction "SHIELD_S4") (pintype "passive"))
      (node (ref "LED_STATUS") (pin "C") (pinfunction "C_C") (pintype "passive"))
      (node (ref "Q_CW") (pin "2") (pinfunction "S_2") (pintype "passive"))
      (node (ref "Q_WW") (pin "2") (pinfunction "S_2") (pintype "passive"))
      (node (ref "R_CC1") (pin "2") (pinfunction "2_2") (pintype "passive"))
      (node (ref "R_CC2") (pin "2") (pinfunction "2_2") (pintype "passive"))
      (node (ref "R_FBB") (pin "2") (pinfunction "2_2") (pintype "passive"))
      (node (ref "R_PDC") (pin "2") (pinfunction "2_2") (pintype "passive"))
      (node (ref "R_PDW") (pin "2") (pinfunction "2_2") (pintype "passive"))
      (node (ref "R_Q1") (pin "2") (pinfunction "2_2") (pintype "passive"))
      (node (ref "SW_BOOT") (pin "2") (pinfunction "2_2") (pintype "passive"))
      (node (ref "SW_BOOT") (pin "4") (pinfunction "2_4") (pintype "passive"))
      (node (ref "SW_RST") (pin "2") (pinfunction "2_2") (pintype "passive"))
      (node (ref "SW_RST") (pin "4") (pinfunction "2_4") (pintype "passive"))
      (node (ref "TVS1") (pin "A") (pinfunction "A_A") (pintype "passive"))
      (node (ref "U_BUCK") (pin "1") (pinfunction "GND_1") (pintype "passive"))
      (node (ref "U_DRV") (pin "10") (pinfunction "PGND3_10") (pintype "power_in"))
      (node (ref "U_DRV") (pin "12") (pinfunction "COMPP_12") (pintype "input"))
      (node (ref "U_DRV") (pin "13") (pinfunction "COMPN_13") (pintype "input"))
      (node (ref "U_DRV") (pin "14") (pinfunction "GND_14") (pintype "power_in"))
      (node (ref "U_DRV") (pin "19") (pinfunction "~{COMPO}_19") (pintype "output"))
      (node (ref "U_DRV") (pin "20") (pinfunction "GND_20") (pintype "power_in"))
      (node (ref "U_DRV") (pin "28") (pinfunction "GND_28") (pintype "power_in"))
      (node (ref "U_DRV") (pin "29") (pinfunction "EXP_29") (pintype "power_in"))
      (node (ref "U_DRV") (pin "6") (pinfunction "PGND1_6") (pintype "power_in"))
      (node (ref "U_DRV") (pin "7") (pinfunction "PGND2_7") (pintype "power_in"))
      (node (ref "U_MCU") (pin "1") (pinfunction "GND_1") (pintype "power_in"))
      (node (ref "U_MCU") (pin "40") (pinfunction "GND_40") (pintype "power_in"))
      (node (ref "U_MCU") (pin "41_1") (pinfunction "GND_41_1") (pintype "power_in"))
      (node (ref "U_MCU") (pin "41_2") (pinfunction "GND_41_2") (pintype "power_in"))
      (node (ref "U_MCU") (pin "41_3") (pinfunction "GND_41_3") (pintype "power_in"))
      (node (ref "U_MCU") (pin "41_4") (pinfunction "GND_41_4") (pintype "power_in"))
      (node (ref "U_MCU") (pin "41_5") (pinfunction "GND_41_5") (pintype "power_in"))
      (node (ref "U_MCU") (pin "41_6") (pinfunction "GND_41_6") (pintype "power_in"))
      (node (ref "U_MCU") (pin "41_7") (pinfunction "GND_41_7") (pintype "power_in"))
      (node (ref "U_MCU") (pin "41_8") (pinfunction "GND_41_8") (pintype "power_in"))
      (node (ref "U_MCU") (pin "41_9") (pinfunction "GND_41_9") (pintype "power_in"))
    )
    (net (code "26") (name "/GW_G") (class "Default")
      (node (ref "Q_WW") (pin "1") (pinfunction "G_1") (pintype "passive"))
      (node (ref "R_GW") (pin "1") (pinfunction "1_1") (pintype "passive"))
      (node (ref "R_PDW") (pin "1") (pinfunction "1_1") (pintype "passive"))
    )
    (net (code "27") (name "/LEDCW") (class "Default")
      (node (ref "R_GC") (pin "2") (pinfunction "2_2") (pintype "passive"))
      (node (ref "U_MCU") (pin "20") (pinfunction "IO12_20") (pintype "bidirectional"))
    )
    (net (code "28") (name "/LEDC_D") (class "Default")
      (node (ref "D_CLC") (pin "A") (pinfunction "A_A") (pintype "passive"))
      (node (ref "J_LED") (pin "3") (pinfunction "C_3") (pintype "passive"))
      (node (ref "Q_CW") (pin "3") (pinfunction "D_3") (pintype "passive"))
    )
    (net (code "29") (name "/LEDWW") (class "Default")
      (node (ref "R_GW") (pin "2") (pinfunction "2_2") (pintype "passive"))
      (node (ref "U_MCU") (pin "19") (pinfunction "IO11_19") (pintype "bidirectional"))
    )
    (net (code "30") (name "/LEDW_D") (class "Default")
      (node (ref "D_CLW") (pin "A") (pinfunction "A_A") (pintype "passive"))
      (node (ref "J_LED") (pin "2") (pinfunction "W_2") (pintype "passive"))
      (node (ref "Q_WW") (pin "3") (pinfunction "D_3") (pintype "passive"))
    )
    (net (code "31") (name "/MOT_U") (class "Default")
      (node (ref "J_MOTOR") (pin "1") (pinfunction "U_1") (pintype "passive"))
      (node (ref "U_DRV") (pin "5") (pinfunction "OUT1_5") (pintype "output"))
    )
    (net (code "32") (name "/MOT_V") (class "Default")
      (node (ref "J_MOTOR") (pin "2") (pinfunction "V_2") (pintype "passive"))
      (node (ref "U_DRV") (pin "8") (pinfunction "OUT2_8") (pintype "output"))
    )
    (net (code "33") (name "/MOT_W") (class "Default")
      (node (ref "J_MOTOR") (pin "3") (pinfunction "W_3") (pintype "passive"))
      (node (ref "U_DRV") (pin "9") (pinfunction "OUT3_9") (pintype "output"))
    )
    (net (code "34") (name "/NFAULT") (class "Default")
      (node (ref "R_NFAULT") (pin "2") (pinfunction "2_2") (pintype "passive"))
      (node (ref "U_DRV") (pin "18") (pinfunction "~{FAULT}_18") (pintype "output"))
      (node (ref "U_MCU") (pin "9") (pinfunction "IO16_9") (pintype "bidirectional"))
    )
    (net (code "35") (name "/NRESET") (class "Default")
      (node (ref "R_NRESET") (pin "2") (pinfunction "2_2") (pintype "passive"))
      (node (ref "U_DRV") (pin "16") (pinfunction "~{RESET}_16") (pintype "input"))
    )
    (net (code "36") (name "/NSLEEP") (class "Default")
      (node (ref "R_NSLEEP") (pin "2") (pinfunction "2_2") (pintype "passive"))
      (node (ref "U_DRV") (pin "17") (pinfunction "~{SLEEP}_17") (pintype "input"))
      (node (ref "U_MCU") (pin "7") (pinfunction "IO7_7") (pintype "bidirectional"))
    )
    (net (code "37") (name "/P3V3") (class "Default")
      (node (ref "C_FF") (pin "1") (pinfunction "1_1") (pintype "passive"))
      (node (ref "C_MCU1") (pin "1") (pinfunction "1_1") (pintype "passive"))
      (node (ref "C_MCU2") (pin "1") (pinfunction "1_1") (pintype "passive"))
      (node (ref "C_MCU3") (pin "1") (pinfunction "1_1") (pintype "passive"))
      (node (ref "C_MCU4") (pin "1") (pinfunction "1_1") (pintype "passive"))
      (node (ref "C_MCU_BULK") (pin "1") (pinfunction "1_1") (pintype "passive"))
      (node (ref "C_OUT1") (pin "1") (pinfunction "1_1") (pintype "passive"))
      (node (ref "C_OUT2") (pin "1") (pinfunction "1_1") (pintype "passive"))
      (node (ref "C_SENS") (pin "1") (pinfunction "1_1") (pintype "passive"))
      (node (ref "D_MCU") (pin "C") (pinfunction "C_C") (pintype "passive"))
      (node (ref "J_EXP") (pin "1") (pinfunction "3V3_1") (pintype "passive"))
      (node (ref "J_PROG") (pin "1") (pinfunction "3V3_1") (pintype "passive"))
      (node (ref "J_SENSOR") (pin "1") (pinfunction "VCC_1") (pintype "passive"))
      (node (ref "L1") (pin "2") (pinfunction "2_2") (pintype "passive"))
      (node (ref "R_AZ_A") (pin "1") (pinfunction "1_1") (pintype "passive"))
      (node (ref "R_AZ_B") (pin "1") (pinfunction "1_1") (pintype "passive"))
      (node (ref "R_AZ_C") (pin "1") (pinfunction "1_1") (pintype "passive"))
      (node (ref "R_BOOT") (pin "1") (pinfunction "1_1") (pintype "passive"))
      (node (ref "R_EN") (pin "1") (pinfunction "1_1") (pintype "passive"))
      (node (ref "R_EN_DRV") (pin "1") (pinfunction "1_1") (pintype "passive"))
      (node (ref "R_FBT") (pin "1") (pinfunction "1_1") (pintype "passive"))
      (node (ref "R_NFAULT") (pin "1") (pinfunction "1_1") (pintype "passive"))
      (node (ref "R_NRESET") (pin "1") (pinfunction "1_1") (pintype "passive"))
      (node (ref "R_NSLEEP") (pin "1") (pinfunction "1_1") (pintype "passive"))
      (node (ref "U_MCU") (pin "2") (pinfunction "3V3_2") (pintype "power_in"))
    )
    (net (code "38") (name "/P24") (class "Default")
      (node (ref "C_IN1") (pin "1") (pinfunction "1_1") (pintype "passive"))
      (node (ref "C_IN2") (pin "1") (pinfunction "1_1") (pintype "passive"))
      (node (ref "C_IN_BULK") (pin "1") (pinfunction "1_1") (pintype "passive"))
      (node (ref "C_VCP") (pin "2") (pinfunction "2_2") (pintype "passive"))
      (node (ref "C_VM1") (pin "1") (pinfunction "1_1") (pintype "passive"))
      (node (ref "C_VM2") (pin "1") (pinfunction "1_1") (pintype "passive"))
      (node (ref "C_VM_BULK") (pin "1") (pinfunction "1_1") (pintype "passive"))
      (node (ref "D_CLC") (pin "C") (pinfunction "C_C") (pintype "passive"))
      (node (ref "D_CLW") (pin "C") (pinfunction "C_C") (pintype "passive"))
      (node (ref "D_OR_USB") (pin "C") (pinfunction "C_C") (pintype "passive"))
      (node (ref "D_Q1") (pin "C") (pinfunction "C_C") (pintype "passive"))
      (node (ref "J_LED") (pin "1") (pinfunction "VP_1") (pintype "passive"))
      (node (ref "Q1") (pin "2") (pinfunction "S_2") (pintype "passive"))
      (node (ref "R_ENB") (pin "1") (pinfunction "1_1") (pintype "passive"))
      (node (ref "TVS1") (pin "C") (pinfunction "C_C") (pintype "passive"))
      (node (ref "U_BUCK") (pin "3") (pinfunction "VIN_3") (pintype "passive"))
      (node (ref "U_DRV") (pin "11") (pinfunction "VM_11") (pintype "power_in"))
      (node (ref "U_DRV") (pin "4") (pinfunction "VM_4") (pintype "power_in"))
    )
    (net (code "39") (name "/P24_F") (class "Default")
      (node (ref "F1") (pin "2") (pinfunction "2_2") (pintype "passive"))
      (node (ref "Q1") (pin "3") (pinfunction "D_3") (pintype "passive"))
    )
    (net (code "40") (name "/P24_RAW") (class "Default")
      (node (ref "F1") (pin "1") (pinfunction "1_1") (pintype "passive"))
      (node (ref "J_PWR") (pin "1") (pinfunction "VP_1") (pintype "passive"))
    )
    (net (code "41") (name "/PWMA") (class "Default")
      (node (ref "U_DRV") (pin "27") (pinfunction "IN1_27") (pintype "input"))
      (node (ref "U_MCU") (pin "4") (pinfunction "IO4_4") (pintype "bidirectional"))
    )
    (net (code "42") (name "/PWMB") (class "Default")
      (node (ref "U_DRV") (pin "25") (pinfunction "IN2_25") (pintype "input"))
      (node (ref "U_MCU") (pin "5") (pinfunction "IO5_5") (pintype "bidirectional"))
    )
    (net (code "43") (name "/PWMC") (class "Default")
      (node (ref "U_DRV") (pin "23") (pinfunction "IN3_23") (pintype "input"))
      (node (ref "U_MCU") (pin "6") (pinfunction "IO6_6") (pintype "bidirectional"))
    )
    (net (code "44") (name "/Q1G") (class "Default")
      (node (ref "D_Q1") (pin "A") (pinfunction "A_A") (pintype "passive"))
      (node (ref "Q1") (pin "1") (pinfunction "G_1") (pintype "passive"))
      (node (ref "R_Q1") (pin "1") (pinfunction "1_1") (pintype "passive"))
    )
    (net (code "45") (name "/ROTA") (class "Default")
      (node (ref "J_KNOB") (pin "1") (pinfunction "A_1") (pintype "passive"))
      (node (ref "U_MCU") (pin "12") (pinfunction "IO8_12") (pintype "bidirectional"))
    )
    (net (code "46") (name "/ROTB") (class "Default")
      (node (ref "J_KNOB") (pin "2") (pinfunction "B_2") (pintype "passive"))
      (node (ref "U_MCU") (pin "17") (pinfunction "IO9_17") (pintype "bidirectional"))
    )
    (net (code "47") (name "/STAT") (class "Default")
      (node (ref "R_STATUS") (pin "1") (pinfunction "1_1") (pintype "passive"))
      (node (ref "U_MCU") (pin "23") (pinfunction "IO21_23") (pintype "bidirectional"))
    )
    (net (code "48") (name "/STAT_A") (class "Default")
      (node (ref "LED_STATUS") (pin "A") (pinfunction "A_A") (pintype "passive"))
      (node (ref "R_STATUS") (pin "2") (pinfunction "2_2") (pintype "passive"))
    )
    (net (code "49") (name "/SW") (class "Default")
      (node (ref "C_BOOT_B") (pin "2") (pinfunction "2_2") (pintype "passive"))
      (node (ref "L1") (pin "1") (pinfunction "1_1") (pintype "passive"))
      (node (ref "U_BUCK") (pin "2") (pinfunction "SW_2") (pintype "passive"))
    )
    (net (code "50") (name "/U0RXD") (class "Default")
      (node (ref "J_PROG") (pin "6") (pinfunction "RXD_6") (pintype "passive"))
      (node (ref "U_MCU") (pin "36") (pinfunction "RXD0_36") (pintype "bidirectional"))
    )
    (net (code "51") (name "/U0TXD") (class "Default")
      (node (ref "J_PROG") (pin "5") (pinfunction "TXD_5") (pintype "passive"))
      (node (ref "U_MCU") (pin "37") (pinfunction "TXD0_37") (pintype "bidirectional"))
    )
    (net (code "52") (name "/USBDM_RAW") (class "Default")
      (node (ref "D_USB") (pin "1") (pinfunction "I/O1_IN_1") (pintype "bidirectional"))
      (node (ref "D_USB") (pin "6") (pinfunction "I/O1_OUT_6") (pintype "bidirectional"))
      (node (ref "J_USB") (pin "A7") (pinfunction "DN1_A7") (pintype "bidirectional"))
      (node (ref "J_USB") (pin "B7") (pinfunction "DN2_B7") (pintype "bidirectional"))
      (node (ref "R_DM") (pin "1") (pinfunction "1_1") (pintype "passive"))
    )
    (net (code "53") (name "/USBDP_RAW") (class "Default")
      (node (ref "D_USB") (pin "3") (pinfunction "I/O2_IN_3") (pintype "bidirectional"))
      (node (ref "D_USB") (pin "4") (pinfunction "I/O2_OUT_4") (pintype "bidirectional"))
      (node (ref "J_USB") (pin "A6") (pinfunction "DP1_A6") (pintype "bidirectional"))
      (node (ref "J_USB") (pin "B6") (pinfunction "DP2_B6") (pintype "bidirectional"))
      (node (ref "R_DP") (pin "1") (pinfunction "1_1") (pintype "passive"))
    )
    (net (code "54") (name "/USB_DM_MCU") (class "Default")
      (node (ref "R_DM") (pin "2") (pinfunction "2_2") (pintype "passive"))
      (node (ref "U_MCU") (pin "13") (pinfunction "IO19_13") (pintype "bidirectional"))
    )
    (net (code "55") (name "/USB_DP_MCU") (class "Default")
      (node (ref "R_DP") (pin "2") (pinfunction "2_2") (pintype "passive"))
      (node (ref "U_MCU") (pin "14") (pinfunction "IO20_14") (pintype "bidirectional"))
    )
    (net (code "56") (name "/VBUS") (class "Default")
      (node (ref "C_VBUS") (pin "1") (pinfunction "1_1") (pintype "passive"))
      (node (ref "D_OR_USB") (pin "A") (pinfunction "A_A") (pintype "passive"))
      (node (ref "D_USB") (pin "5") (pinfunction "VBUS_5") (pintype "power_in"))
      (node (ref "J_USB") (pin "A4_B9") (pinfunction "VBUS_A4_B9") (pintype "power_in"))
      (node (ref "J_USB") (pin "B4_A9") (pinfunction "VBUS_B4_A9") (pintype "power_in"))
    )
    (net (code "57") (name "/VCP") (class "Default")
      (node (ref "C_VCP") (pin "1") (pinfunction "1_1") (pintype "passive"))
      (node (ref "U_DRV") (pin "3") (pinfunction "VCP_3") (pintype "power_in"))
    )
    (net (code "58") (name "unconnected-(J_USB-SBU1-PadA8)") (class "Default")
      (node (ref "J_USB") (pin "A8") (pinfunction "SBU1_A8") (pintype "bidirectional"))
    )
    (net (code "59") (name "unconnected-(J_USB-SBU2-PadB8)") (class "Default")
      (node (ref "J_USB") (pin "B8") (pinfunction "SBU2_B8") (pintype "bidirectional"))
    )
    (net (code "60") (name "unconnected-(U_DRV-NC-Pad21)") (class "Default")
      (node (ref "U_DRV") (pin "21") (pinfunction "NC_21") (pintype "no_connect"))
    )
    (net (code "61") (name "unconnected-(U_MCU-IO3-Pad15)") (class "Default")
      (node (ref "U_MCU") (pin "15") (pinfunction "IO3_15") (pintype "bidirectional"))
    )
    (net (code "62") (name "unconnected-(U_MCU-IO35-Pad28)") (class "Default")
      (node (ref "U_MCU") (pin "28") (pinfunction "IO35_28") (pintype "bidirectional"))
    )
    (net (code "63") (name "unconnected-(U_MCU-IO36-Pad29)") (class "Default")
      (node (ref "U_MCU") (pin "29") (pinfunction "IO36_29") (pintype "bidirectional"))
    )
    (net (code "64") (name "unconnected-(U_MCU-IO37-Pad30)") (class "Default")
      (node (ref "U_MCU") (pin "30") (pinfunction "IO37_30") (pintype "bidirectional"))
    )
    (net (code "65") (name "unconnected-(U_MCU-IO45-Pad26)") (class "Default")
      (node (ref "U_MCU") (pin "26") (pinfunction "IO45_26") (pintype "bidirectional"))
    )
    (net (code "66") (name "unconnected-(U_MCU-IO46-Pad16)") (class "Default")
      (node (ref "U_MCU") (pin "16") (pinfunction "IO46_16") (pintype "bidirectional"))
    )
    (net (code "67") (name "unconnected-(U_MCU-IO47-Pad24)") (class "Default")
      (node (ref "U_MCU") (pin "24") (pinfunction "IO47_24") (pintype "bidirectional"))
    )
    (net (code "68") (name "unconnected-(U_MCU-IO48-Pad25)") (class "Default")
      (node (ref "U_MCU") (pin "25") (pinfunction "IO48_25") (pintype "bidirectional"))
    )
  )
)
